# Sheet1.net
KiCad netlist of a schematic drawn in Altium Designer
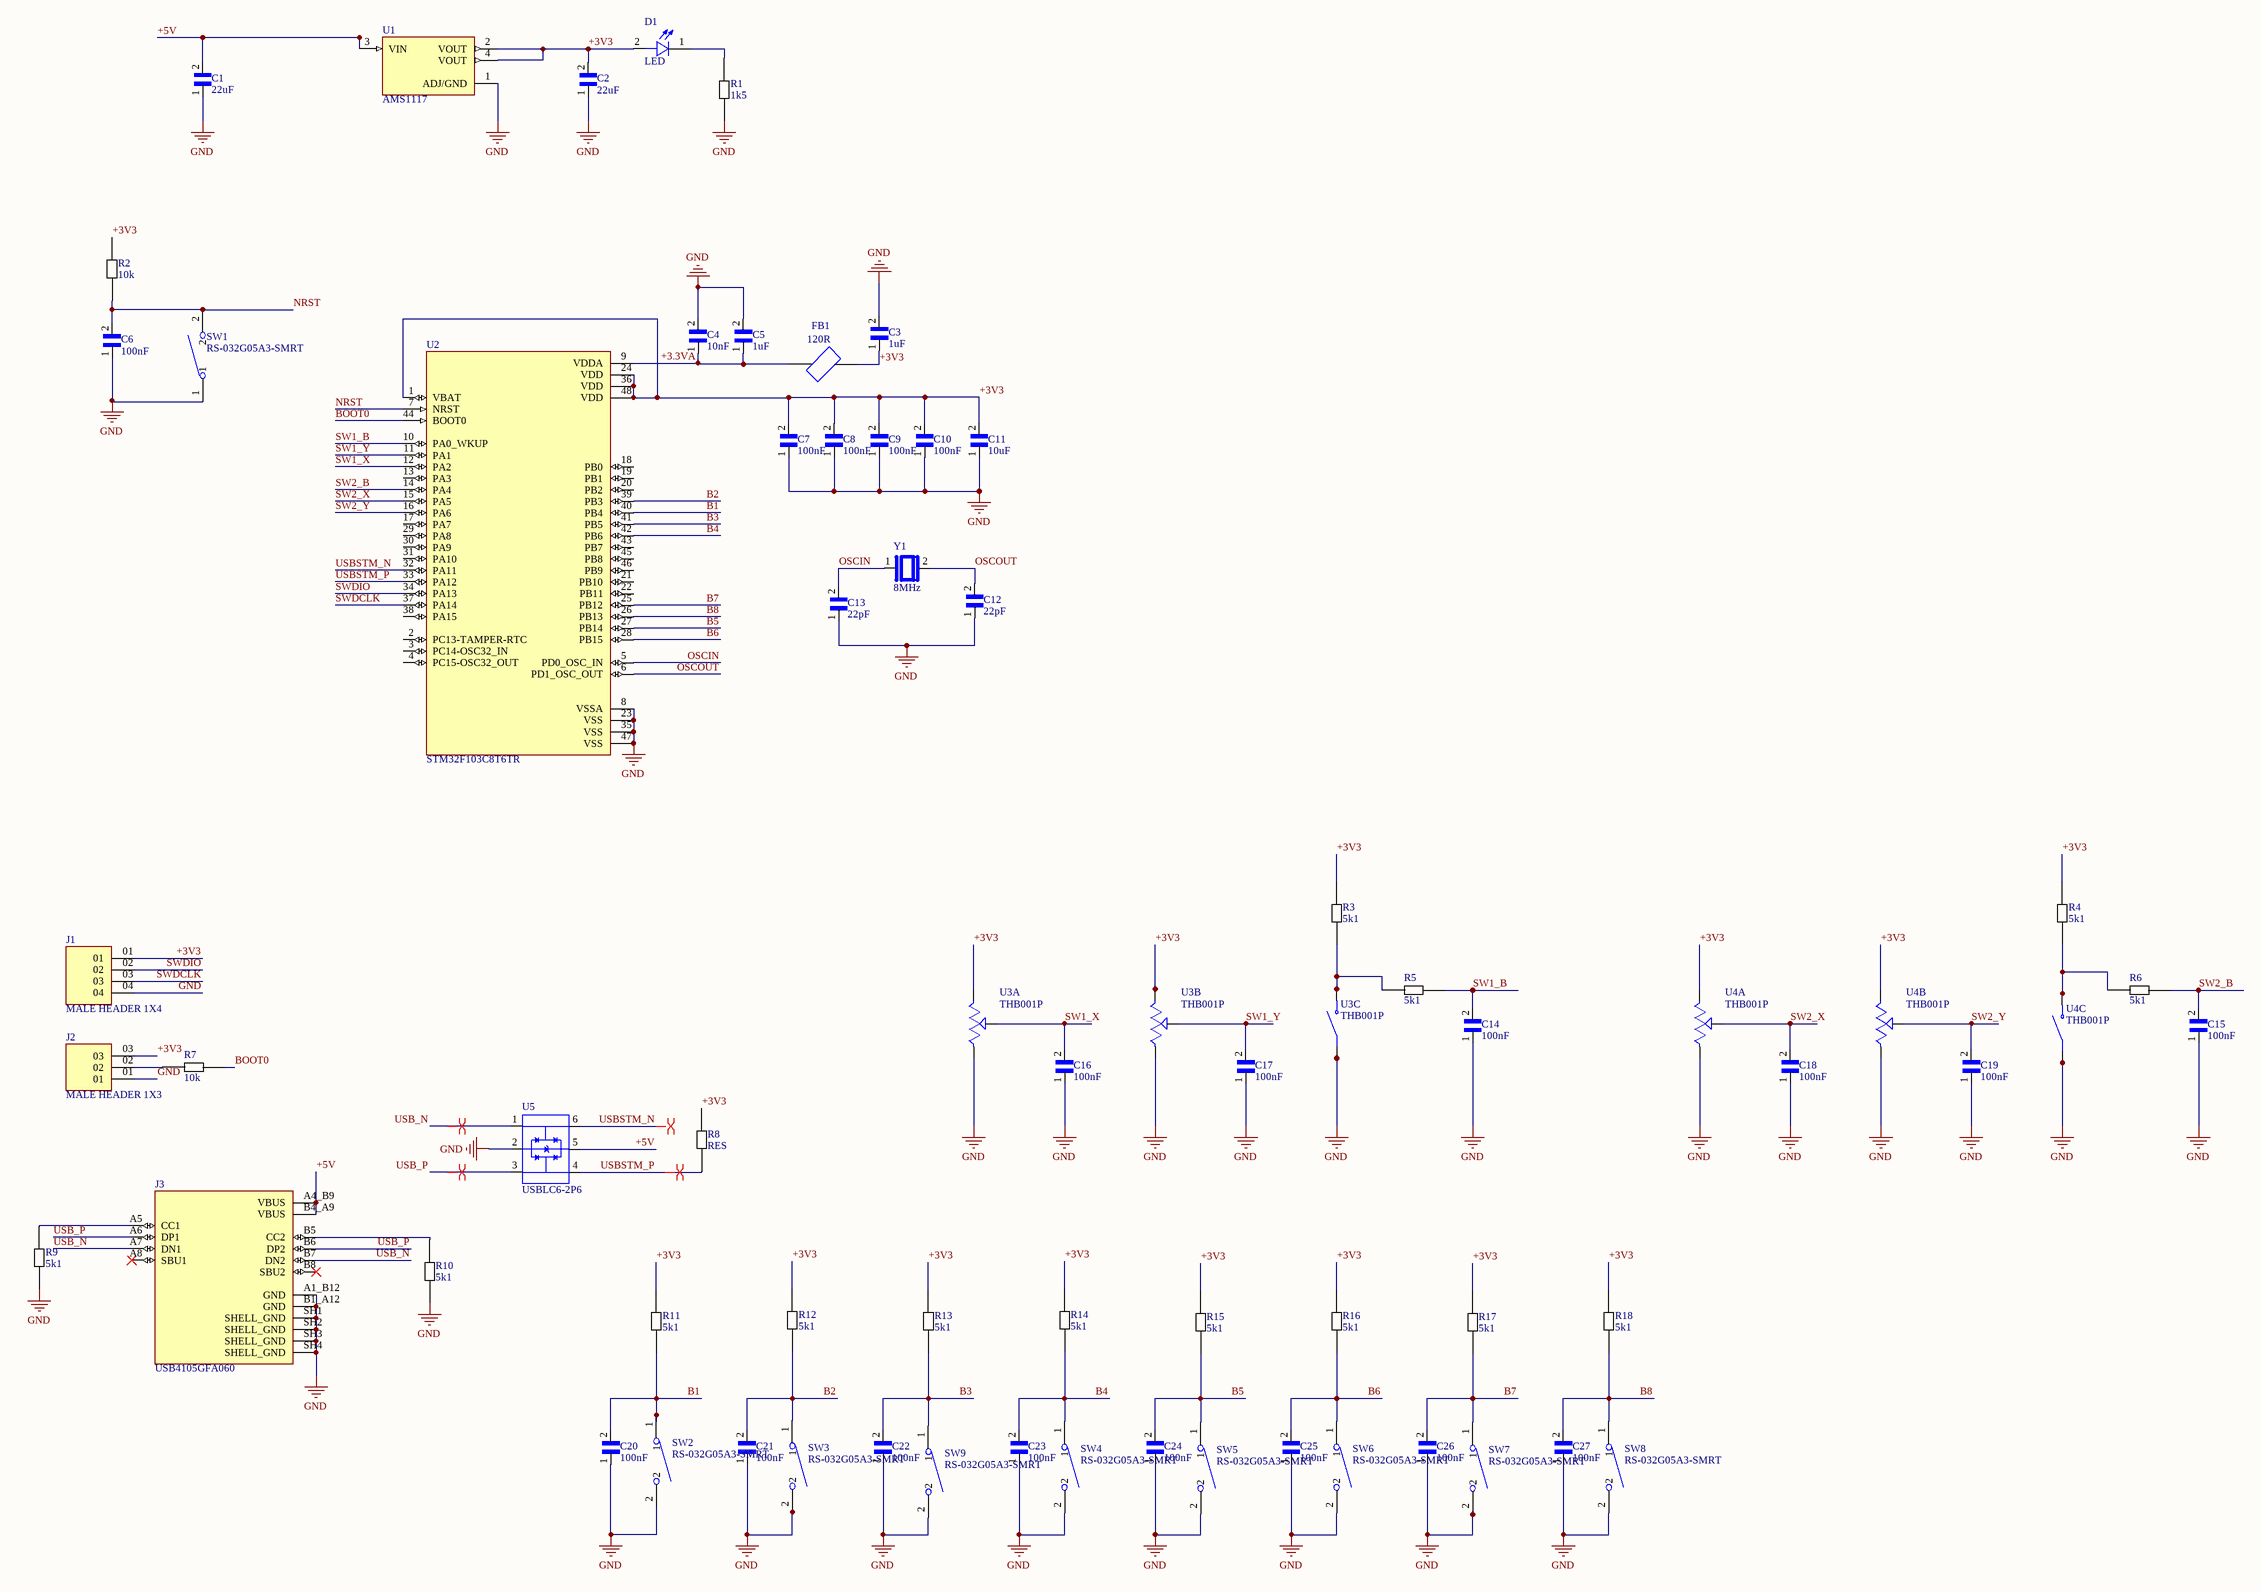
[diagram p0: Sheet1.SchDoc]

(export (version "E")
  (design (tool "Eeschema 10.0.6"))
  (components
    (comp (ref "C1")
      (value "22uF")
      (footprint "CAPC2012X94N")
      (description "10000pF Â±5% 16V Ceramic Capacitor X7R 0805 _2012 Metric_")
      (fields (field (name "MF") "AVX") (field (name "MP") "0805YC103J4T2A"))
      (libsource (lib "Schlib1") (part "CAP"))
    )
    (comp (ref "C2")
      (value "22uF")
      (footprint "CAPC2012X94N")
      (description "10000pF Â±5% 16V Ceramic Capacitor X7R 0805 _2012 Metric_")
      (fields (field (name "MF") "AVX") (field (name "MP") "0805YC103J4T2A"))
      (libsource (lib "Schlib1") (part "CAP"))
    )
    (comp (ref "C3")
      (value "1uF")
      (footprint "CAPC2012X94N")
      (description "10000pF Â±5% 16V Ceramic Capacitor X7R 0805 _2012 Metric_")
      (fields (field (name "MF") "AVX") (field (name "MP") "0805YC103J4T2A"))
      (libsource (lib "Schlib1") (part "CAP"))
    )
    (comp (ref "C4")
      (value "10nF")
      (footprint "CAPC2012X94N")
      (description "10000pF Â±5% 16V Ceramic Capacitor X7R 0805 _2012 Metric_")
      (fields (field (name "MF") "AVX") (field (name "MP") "0805YC103J4T2A"))
      (libsource (lib "Schlib1") (part "CAP"))
    )
    (comp (ref "C5")
      (value "1uF")
      (footprint "CAPC2012X94N")
      (description "10000pF Â±5% 16V Ceramic Capacitor X7R 0805 _2012 Metric_")
      (fields (field (name "MF") "AVX") (field (name "MP") "0805YC103J4T2A"))
      (libsource (lib "Schlib1") (part "CAP"))
    )
    (comp (ref "C6")
      (value "100nF")
      (footprint "CAPC2012X94N")
      (description "10000pF Â±5% 16V Ceramic Capacitor X7R 0805 _2012 Metric_")
      (fields (field (name "MF") "AVX") (field (name "MP") "0805YC103J4T2A"))
      (libsource (lib "Schlib1") (part "CAP"))
    )
    (comp (ref "C7")
      (value "100nF")
      (footprint "CAPC2012X94N")
      (description "10000pF Â±5% 16V Ceramic Capacitor X7R 0805 _2012 Metric_")
      (fields (field (name "MF") "AVX") (field (name "MP") "0805YC103J4T2A"))
      (libsource (lib "Schlib1") (part "CAP"))
    )
    (comp (ref "C8")
      (value "100nF")
      (footprint "CAPC2012X94N")
      (description "10000pF Â±5% 16V Ceramic Capacitor X7R 0805 _2012 Metric_")
      (fields (field (name "MF") "AVX") (field (name "MP") "0805YC103J4T2A"))
      (libsource (lib "Schlib1") (part "CAP"))
    )
    (comp (ref "C9")
      (value "100nF")
      (footprint "CAPC2012X94N")
      (description "10000pF Â±5% 16V Ceramic Capacitor X7R 0805 _2012 Metric_")
      (fields (field (name "MF") "AVX") (field (name "MP") "0805YC103J4T2A"))
      (libsource (lib "Schlib1") (part "CAP"))
    )
    (comp (ref "C10")
      (value "100nF")
      (footprint "CAPC2012X94N")
      (description "10000pF Â±5% 16V Ceramic Capacitor X7R 0805 _2012 Metric_")
      (fields (field (name "MF") "AVX") (field (name "MP") "0805YC103J4T2A"))
      (libsource (lib "Schlib1") (part "CAP"))
    )
    (comp (ref "C11")
      (value "10uF")
      (footprint "CAPC2012X94N")
      (description "10000pF Â±5% 16V Ceramic Capacitor X7R 0805 _2012 Metric_")
      (fields (field (name "MF") "AVX") (field (name "MP") "0805YC103J4T2A"))
      (libsource (lib "Schlib1") (part "CAP"))
    )
    (comp (ref "C12")
      (value "22pF")
      (footprint "CAPC2012X94N")
      (description "10000pF Â±5% 16V Ceramic Capacitor X7R 0805 _2012 Metric_")
      (fields (field (name "MF") "AVX") (field (name "MP") "0805YC103J4T2A"))
      (libsource (lib "Schlib1") (part "CAP"))
    )
    (comp (ref "C13")
      (value "22pF")
      (footprint "CAPC2012X94N")
      (description "10000pF Â±5% 16V Ceramic Capacitor X7R 0805 _2012 Metric_")
      (fields (field (name "MF") "AVX") (field (name "MP") "0805YC103J4T2A"))
      (libsource (lib "Schlib1") (part "CAP"))
    )
    (comp (ref "C14")
      (value "100nF")
      (footprint "CAPC2012X94N")
      (description "10000pF Â±5% 16V Ceramic Capacitor X7R 0805 _2012 Metric_")
      (fields (field (name "MF") "AVX") (field (name "MP") "0805YC103J4T2A"))
      (libsource (lib "Schlib1") (part "CAP"))
    )
    (comp (ref "C15")
      (value "100nF")
      (footprint "CAPC2012X94N")
      (description "10000pF Â±5% 16V Ceramic Capacitor X7R 0805 _2012 Metric_")
      (fields (field (name "MF") "AVX") (field (name "MP") "0805YC103J4T2A"))
      (libsource (lib "Schlib1") (part "CAP"))
    )
    (comp (ref "C16")
      (value "100nF")
      (footprint "CAPC2012X94N")
      (description "10000pF Â±5% 16V Ceramic Capacitor X7R 0805 _2012 Metric_")
      (fields (field (name "MF") "AVX") (field (name "MP") "0805YC103J4T2A"))
      (libsource (lib "Schlib1") (part "CAP"))
    )
    (comp (ref "C17")
      (value "100nF")
      (footprint "CAPC2012X94N")
      (description "10000pF Â±5% 16V Ceramic Capacitor X7R 0805 _2012 Metric_")
      (fields (field (name "MF") "AVX") (field (name "MP") "0805YC103J4T2A"))
      (libsource (lib "Schlib1") (part "CAP"))
    )
    (comp (ref "C18")
      (value "100nF")
      (footprint "CAPC2012X94N")
      (description "10000pF Â±5% 16V Ceramic Capacitor X7R 0805 _2012 Metric_")
      (fields (field (name "MF") "AVX") (field (name "MP") "0805YC103J4T2A"))
      (libsource (lib "Schlib1") (part "CAP"))
    )
    (comp (ref "C19")
      (value "100nF")
      (footprint "CAPC2012X94N")
      (description "10000pF Â±5% 16V Ceramic Capacitor X7R 0805 _2012 Metric_")
      (fields (field (name "MF") "AVX") (field (name "MP") "0805YC103J4T2A"))
      (libsource (lib "Schlib1") (part "CAP"))
    )
    (comp (ref "C20")
      (value "100nF")
      (footprint "CAPC2012X94N")
      (description "10000pF Â±5% 16V Ceramic Capacitor X7R 0805 _2012 Metric_")
      (fields (field (name "MF") "AVX") (field (name "MP") "0805YC103J4T2A"))
      (libsource (lib "Schlib1") (part "CAP"))
    )
    (comp (ref "C21")
      (value "100nF")
      (footprint "CAPC2012X94N")
      (description "10000pF Â±5% 16V Ceramic Capacitor X7R 0805 _2012 Metric_")
      (fields (field (name "MF") "AVX") (field (name "MP") "0805YC103J4T2A"))
      (libsource (lib "Schlib1") (part "CAP"))
    )
    (comp (ref "C22")
      (value "100nF")
      (footprint "CAPC2012X94N")
      (description "10000pF Â±5% 16V Ceramic Capacitor X7R 0805 _2012 Metric_")
      (fields (field (name "MF") "AVX") (field (name "MP") "0805YC103J4T2A"))
      (libsource (lib "Schlib1") (part "CAP"))
    )
    (comp (ref "C23")
      (value "100nF")
      (footprint "CAPC2012X94N")
      (description "10000pF Â±5% 16V Ceramic Capacitor X7R 0805 _2012 Metric_")
      (fields (field (name "MF") "AVX") (field (name "MP") "0805YC103J4T2A"))
      (libsource (lib "Schlib1") (part "CAP"))
    )
    (comp (ref "C24")
      (value "100nF")
      (footprint "CAPC2012X94N")
      (description "10000pF Â±5% 16V Ceramic Capacitor X7R 0805 _2012 Metric_")
      (fields (field (name "MF") "AVX") (field (name "MP") "0805YC103J4T2A"))
      (libsource (lib "Schlib1") (part "CAP"))
    )
    (comp (ref "C25")
      (value "100nF")
      (footprint "CAPC2012X94N")
      (description "10000pF Â±5% 16V Ceramic Capacitor X7R 0805 _2012 Metric_")
      (fields (field (name "MF") "AVX") (field (name "MP") "0805YC103J4T2A"))
      (libsource (lib "Schlib1") (part "CAP"))
    )
    (comp (ref "C26")
      (value "100nF")
      (footprint "CAPC2012X94N")
      (description "10000pF Â±5% 16V Ceramic Capacitor X7R 0805 _2012 Metric_")
      (fields (field (name "MF") "AVX") (field (name "MP") "0805YC103J4T2A"))
      (libsource (lib "Schlib1") (part "CAP"))
    )
    (comp (ref "C27")
      (value "100nF")
      (footprint "CAPC2012X94N")
      (description "10000pF Â±5% 16V Ceramic Capacitor X7R 0805 _2012 Metric_")
      (fields (field (name "MF") "AVX") (field (name "MP") "0805YC103J4T2A"))
      (libsource (lib "Schlib1") (part "CAP"))
    )
    (comp (ref "D1")
      (value "LED")
      (footprint "LED_V0805-SMD-R (Red)")
      (description "V0805 - Valcon 0805 Type Surface Mount LED")
      (fields (field (name "MF") "Valcon") (field (name "MP") "V0805-SMD-R (Red)"))
      (libsource (lib "Schlib1") (part "LED"))
    )
    (comp (ref "FB1")
      (value "120R")
      (footprint "FB_MI0805K400R-10")
      (description "40 Ohms @ 100MHz 1 Power Line Ferrite Bead 0805 (2012 Metric) 1.5A 50mOhm")
      (fields (field (name "MP") "MI0805K400R-10") (field (name "MF") "Laird-Signal Integrity Products"))
      (libsource (lib "Schlib1") (part "FB"))
    )
    (comp (ref "J1")
      (value "MALE HEADER 1X4")
      (footprint "SAMTEC_MTLW-104-X-X-S-X")
      (fields (field (name "MF") "{'manufacturer': u'Samtec Inc.'}") (field (name "MP") "MTLW-104-X-X-S-X"))
      (libsource (lib "Schlib1") (part "MALE HEADER 1X4"))
    )
    (comp (ref "J2")
      (value "MALE HEADER 1X3")
      (footprint "SAMTEC_MTLW-103-XX-XX-S-XXX")
      (description "Connector Header Through Hole 40 position 0.100\" (2.54mm)")
      (fields (field (name "MP") "MTLW-103-XX-XX-S-XXX"))
      (libsource (lib "Schlib1") (part "MALE HEADER 1X3"))
    )
    (comp (ref "J3")
      (value "USB4105GFA060")
      (footprint "GCT_USB4105GFA060")
      (fields (field (name "MF") "{'manufacturer': u'GCT'}"))
      (libsource (lib "Schlib1") (part "USB4105GFA060"))
    )
    (comp (ref "R1")
      (value "1k5")
      (footprint "RESC2012X60N")
      (description "330 Ohms Â±1% 0.125W, 1/8W Chip Resistor 0805 _2012 Metric_ Moisture Resistant Thick Film")
      (fields (field (name "MP") "RC0805FR-07330RL") (field (name "MF") "Yageo"))
      (libsource (lib "Schlib1") (part "RES"))
    )
    (comp (ref "R2")
      (value "10k")
      (footprint "RESC2012X60N")
      (description "330 Ohms Â±1% 0.125W, 1/8W Chip Resistor 0805 _2012 Metric_ Moisture Resistant Thick Film")
      (fields (field (name "MP") "RC0805FR-07330RL") (field (name "MF") "Yageo"))
      (libsource (lib "Schlib1") (part "RES"))
    )
    (comp (ref "R3")
      (value "5k1")
      (footprint "RESC2012X60N")
      (description "330 Ohms Â±1% 0.125W, 1/8W Chip Resistor 0805 _2012 Metric_ Moisture Resistant Thick Film")
      (fields (field (name "MP") "RC0805FR-07330RL") (field (name "MF") "Yageo"))
      (libsource (lib "Schlib1") (part "RES"))
    )
    (comp (ref "R4")
      (value "5k1")
      (footprint "RESC2012X60N")
      (description "330 Ohms Â±1% 0.125W, 1/8W Chip Resistor 0805 _2012 Metric_ Moisture Resistant Thick Film")
      (fields (field (name "MP") "RC0805FR-07330RL") (field (name "MF") "Yageo"))
      (libsource (lib "Schlib1") (part "RES"))
    )
    (comp (ref "R5")
      (value "5k1")
      (footprint "RESC2012X60N")
      (description "330 Ohms Â±1% 0.125W, 1/8W Chip Resistor 0805 _2012 Metric_ Moisture Resistant Thick Film")
      (fields (field (name "MP") "RC0805FR-07330RL") (field (name "MF") "Yageo"))
      (libsource (lib "Schlib1") (part "RES"))
    )
    (comp (ref "R6")
      (value "5k1")
      (footprint "RESC2012X60N")
      (description "330 Ohms Â±1% 0.125W, 1/8W Chip Resistor 0805 _2012 Metric_ Moisture Resistant Thick Film")
      (fields (field (name "MP") "RC0805FR-07330RL") (field (name "MF") "Yageo"))
      (libsource (lib "Schlib1") (part "RES"))
    )
    (comp (ref "R7")
      (value "10k")
      (footprint "RESC2012X60N")
      (description "330 Ohms Â±1% 0.125W, 1/8W Chip Resistor 0805 _2012 Metric_ Moisture Resistant Thick Film")
      (fields (field (name "MP") "RC0805FR-07330RL") (field (name "MF") "Yageo"))
      (libsource (lib "Schlib1") (part "RES"))
    )
    (comp (ref "R8")
      (value "RES")
      (footprint "RESC2012X60N")
      (description "330 Ohms Â±1% 0.125W, 1/8W Chip Resistor 0805 _2012 Metric_ Moisture Resistant Thick Film")
      (fields (field (name "MP") "RC0805FR-07330RL") (field (name "MF") "Yageo"))
      (libsource (lib "Schlib1") (part "RES"))
    )
    (comp (ref "R9")
      (value "5k1")
      (footprint "RESC2012X60N")
      (description "330 Ohms Â±1% 0.125W, 1/8W Chip Resistor 0805 _2012 Metric_ Moisture Resistant Thick Film")
      (fields (field (name "MP") "RC0805FR-07330RL") (field (name "MF") "Yageo"))
      (libsource (lib "Schlib1") (part "RES"))
    )
    (comp (ref "R10")
      (value "5k1")
      (footprint "RESC2012X60N")
      (description "330 Ohms Â±1% 0.125W, 1/8W Chip Resistor 0805 _2012 Metric_ Moisture Resistant Thick Film")
      (fields (field (name "MP") "RC0805FR-07330RL") (field (name "MF") "Yageo"))
      (libsource (lib "Schlib1") (part "RES"))
    )
    (comp (ref "R11")
      (value "5k1")
      (footprint "RESC2012X60N")
      (description "330 Ohms Â±1% 0.125W, 1/8W Chip Resistor 0805 _2012 Metric_ Moisture Resistant Thick Film")
      (fields (field (name "MP") "RC0805FR-07330RL") (field (name "MF") "Yageo"))
      (libsource (lib "Schlib1") (part "RES"))
    )
    (comp (ref "R12")
      (value "5k1")
      (footprint "RESC2012X60N")
      (description "330 Ohms Â±1% 0.125W, 1/8W Chip Resistor 0805 _2012 Metric_ Moisture Resistant Thick Film")
      (fields (field (name "MP") "RC0805FR-07330RL") (field (name "MF") "Yageo"))
      (libsource (lib "Schlib1") (part "RES"))
    )
    (comp (ref "R13")
      (value "5k1")
      (footprint "RESC2012X60N")
      (description "330 Ohms Â±1% 0.125W, 1/8W Chip Resistor 0805 _2012 Metric_ Moisture Resistant Thick Film")
      (fields (field (name "MP") "RC0805FR-07330RL") (field (name "MF") "Yageo"))
      (libsource (lib "Schlib1") (part "RES"))
    )
    (comp (ref "R14")
      (value "5k1")
      (footprint "RESC2012X60N")
      (description "330 Ohms Â±1% 0.125W, 1/8W Chip Resistor 0805 _2012 Metric_ Moisture Resistant Thick Film")
      (fields (field (name "MP") "RC0805FR-07330RL") (field (name "MF") "Yageo"))
      (libsource (lib "Schlib1") (part "RES"))
    )
    (comp (ref "R15")
      (value "5k1")
      (footprint "RESC2012X60N")
      (description "330 Ohms Â±1% 0.125W, 1/8W Chip Resistor 0805 _2012 Metric_ Moisture Resistant Thick Film")
      (fields (field (name "MP") "RC0805FR-07330RL") (field (name "MF") "Yageo"))
      (libsource (lib "Schlib1") (part "RES"))
    )
    (comp (ref "R16")
      (value "5k1")
      (footprint "RESC2012X60N")
      (description "330 Ohms Â±1% 0.125W, 1/8W Chip Resistor 0805 _2012 Metric_ Moisture Resistant Thick Film")
      (fields (field (name "MP") "RC0805FR-07330RL") (field (name "MF") "Yageo"))
      (libsource (lib "Schlib1") (part "RES"))
    )
    (comp (ref "R17")
      (value "5k1")
      (footprint "RESC2012X60N")
      (description "330 Ohms Â±1% 0.125W, 1/8W Chip Resistor 0805 _2012 Metric_ Moisture Resistant Thick Film")
      (fields (field (name "MP") "RC0805FR-07330RL") (field (name "MF") "Yageo"))
      (libsource (lib "Schlib1") (part "RES"))
    )
    (comp (ref "R18")
      (value "5k1")
      (footprint "RESC2012X60N")
      (description "330 Ohms Â±1% 0.125W, 1/8W Chip Resistor 0805 _2012 Metric_ Moisture Resistant Thick Film")
      (fields (field (name "MP") "RC0805FR-07330RL") (field (name "MF") "Yageo"))
      (libsource (lib "Schlib1") (part "RES"))
    )
    (comp (ref "SW1")
      (value "RS-032G05A3-SMRT")
      (footprint "SW_RS-032G05A3-SMRT")
      (description "Tactile Switch SPST-NO Top Actuated Surface Mount")
      (fields (field (name "MF") "C&K") (field (name "MP") "RS032G05A3SMRT"))
      (libsource (lib "Schlib1") (part "RS-032G05A3-SMRT"))
    )
    (comp (ref "SW2")
      (value "RS-032G05A3-SMRT")
      (footprint "SW_RS-032G05A3-SMRT")
      (description "Tactile Switch SPST-NO Top Actuated Surface Mount")
      (fields (field (name "MF") "C&K") (field (name "MP") "RS032G05A3SMRT"))
      (libsource (lib "Schlib1") (part "RS-032G05A3-SMRT"))
    )
    (comp (ref "SW3")
      (value "RS-032G05A3-SMRT")
      (footprint "SW_RS-032G05A3-SMRT")
      (description "Tactile Switch SPST-NO Top Actuated Surface Mount")
      (fields (field (name "MF") "C&K") (field (name "MP") "RS032G05A3SMRT"))
      (libsource (lib "Schlib1") (part "RS-032G05A3-SMRT"))
    )
    (comp (ref "SW4")
      (value "RS-032G05A3-SMRT")
      (footprint "SW_RS-032G05A3-SMRT")
      (description "Tactile Switch SPST-NO Top Actuated Surface Mount")
      (fields (field (name "MF") "C&K") (field (name "MP") "RS032G05A3SMRT"))
      (libsource (lib "Schlib1") (part "RS-032G05A3-SMRT"))
    )
    (comp (ref "SW5")
      (value "RS-032G05A3-SMRT")
      (footprint "SW_RS-032G05A3-SMRT")
      (description "Tactile Switch SPST-NO Top Actuated Surface Mount")
      (fields (field (name "MF") "C&K") (field (name "MP") "RS032G05A3SMRT"))
      (libsource (lib "Schlib1") (part "RS-032G05A3-SMRT"))
    )
    (comp (ref "SW6")
      (value "RS-032G05A3-SMRT")
      (footprint "SW_RS-032G05A3-SMRT")
      (description "Tactile Switch SPST-NO Top Actuated Surface Mount")
      (fields (field (name "MF") "C&K") (field (name "MP") "RS032G05A3SMRT"))
      (libsource (lib "Schlib1") (part "RS-032G05A3-SMRT"))
    )
    (comp (ref "SW7")
      (value "RS-032G05A3-SMRT")
      (footprint "SW_RS-032G05A3-SMRT")
      (description "Tactile Switch SPST-NO Top Actuated Surface Mount")
      (fields (field (name "MF") "C&K") (field (name "MP") "RS032G05A3SMRT"))
      (libsource (lib "Schlib1") (part "RS-032G05A3-SMRT"))
    )
    (comp (ref "SW8")
      (value "RS-032G05A3-SMRT")
      (footprint "SW_RS-032G05A3-SMRT")
      (description "Tactile Switch SPST-NO Top Actuated Surface Mount")
      (fields (field (name "MF") "C&K") (field (name "MP") "RS032G05A3SMRT"))
      (libsource (lib "Schlib1") (part "RS-032G05A3-SMRT"))
    )
    (comp (ref "SW9")
      (value "RS-032G05A3-SMRT")
      (footprint "SW_RS-032G05A3-SMRT")
      (description "Tactile Switch SPST-NO Top Actuated Surface Mount")
      (fields (field (name "MF") "C&K") (field (name "MP") "RS032G05A3SMRT"))
      (libsource (lib "Schlib1") (part "RS-032G05A3-SMRT"))
    )
    (comp (ref "U1")
      (value "AMS1117")
      (footprint "SOT229P700X180-4N")
      (description "1A LOW DROPOUT VOLTAGE REGULATOR SOT-223")
      (fields (field (name "MF") "Advanced Monolithic Systems"))
      (libsource (lib "Schlib1") (part "AMS1117"))
    )
    (comp (ref "U2")
      (value "STM32F103C8T6TR")
      (footprint "QFP50P900X900X160-48N")
      (fields (field (name "MF") "{'manufacturer': u'STMicroelectronics'}"))
      (libsource (lib "Schlib1") (part "STM32F103C8T6TR"))
    )
    (comp (ref "U3")
      (value "THB001P")
      (footprint "CNK_THB001P")
      (description "Joystick, 2 - Axis Analog (Resistive) Output")
      (fields (field (name "MF") "C&K"))
      (libsource (lib "") (part "THB001P_1"))
    )
    (comp (ref "U4")
      (value "THB001P")
      (footprint "CNK_THB001P")
      (description "Joystick, 2 - Axis Analog (Resistive) Output")
      (fields (field (name "MF") "C&K"))
      (libsource (lib "Schlib1") (part "THB001P"))
    )
    (comp (ref "U5")
      (value "USBLC6-2P6")
      (footprint "SOT50P160X60-6N")
      (description "17V Clamp 5A _8/20Âµs_ Ipp Tvs Diode Surface Mount SOT-666")
      (fields (field (name "MF") "STMicroelectronics"))
      (libsource (lib "Schlib1") (part "USBLC6-2P6"))
    )
    (comp (ref "Y1")
      (value "8MHz")
      (footprint "XTAL_HC49P488W43L1150T466H350")
      (description "16 MHz Â±30ppm Crystal 18pF 50 Ohms HC-49/US")
      (fields (field (name "MF") "Citizen Finedevice Co Ltd") (field (name "MP") "HC-49/U-S16000000ABJB"))
      (libsource (lib "Schlib1") (part "HC-49/U-S16000000ABJB"))
    )
  )
  (nets
    (net (code "1") (name "/+3.3VA") (class "Default")
      (node (ref "C4") (pin "1") (pinfunction "1_1") (pintype "passive"))
      (node (ref "C5") (pin "1") (pinfunction "1_1") (pintype "passive"))
      (node (ref "FB1") (pin "1") (pinfunction "1_1") (pintype "passive"))
      (node (ref "U2") (pin "9") (pinfunction "VDDA_9") (pintype "power_in"))
    )
    (net (code "2") (name "/+3V3") (class "Default")
      (node (ref "C10") (pin "2") (pinfunction "2_2") (pintype "passive"))
      (node (ref "C11") (pin "2") (pinfunction "2_2") (pintype "passive"))
      (node (ref "C2") (pin "2") (pinfunction "2_2") (pintype "passive"))
      (node (ref "C3") (pin "1") (pinfunction "1_1") (pintype "passive"))
      (node (ref "C7") (pin "2") (pinfunction "2_2") (pintype "passive"))
      (node (ref "C8") (pin "2") (pinfunction "2_2") (pintype "passive"))
      (node (ref "C9") (pin "2") (pinfunction "2_2") (pintype "passive"))
      (node (ref "D1") (pin "2") (pinfunction "A_2") (pintype "passive"))
      (node (ref "FB1") (pin "2") (pinfunction "2_2") (pintype "passive"))
      (node (ref "J1") (pin "01") (pinfunction "01_01") (pintype "passive"))
      (node (ref "J2") (pin "03") (pinfunction "03_03") (pintype "passive"))
      (node (ref "R11") (pin "2") (pinfunction "2_2") (pintype "passive"))
      (node (ref "R12") (pin "2") (pinfunction "2_2") (pintype "passive"))
      (node (ref "R13") (pin "2") (pinfunction "2_2") (pintype "passive"))
      (node (ref "R14") (pin "2") (pinfunction "2_2") (pintype "passive"))
      (node (ref "R15") (pin "2") (pinfunction "2_2") (pintype "passive"))
      (node (ref "R16") (pin "2") (pinfunction "2_2") (pintype "passive"))
      (node (ref "R17") (pin "2") (pinfunction "2_2") (pintype "passive"))
      (node (ref "R18") (pin "2") (pinfunction "2_2") (pintype "passive"))
      (node (ref "R2") (pin "2") (pinfunction "2_2") (pintype "passive"))
      (node (ref "R3") (pin "2") (pinfunction "2_2") (pintype "passive"))
      (node (ref "R4") (pin "2") (pinfunction "2_2") (pintype "passive"))
      (node (ref "R8") (pin "2") (pinfunction "2_2") (pintype "passive"))
      (node (ref "U1") (pin "2") (pinfunction "VOUT_2") (pintype "output"))
      (node (ref "U1") (pin "4") (pinfunction "VOUT_4") (pintype "output"))
      (node (ref "U2") (pin "1") (pinfunction "VBAT_1") (pintype "bidirectional"))
      (node (ref "U2") (pin "24") (pinfunction "VDD_24") (pintype "power_in"))
      (node (ref "U2") (pin "36") (pinfunction "VDD_36") (pintype "power_in"))
      (node (ref "U2") (pin "48") (pinfunction "VDD_48") (pintype "power_in"))
      (node (ref "U3") (pin "VR1_3") (pinfunction "VR1_3_VR1_3") (pintype "passive"))
      (node (ref "U3") (pin "VR2_3") (pinfunction "VR2_3_VR2_3") (pintype "passive"))
      (node (ref "U4") (pin "VR1_3") (pinfunction "VR1_3_VR1_3") (pintype "passive"))
      (node (ref "U4") (pin "VR2_3") (pinfunction "VR2_3_VR2_3") (pintype "passive"))
    )
    (net (code "3") (name "/+5V") (class "Default")
      (node (ref "C1") (pin "2") (pinfunction "2_2") (pintype "passive"))
      (node (ref "J3") (pin "A4_B9") (pinfunction "VBUS_A4_B9") (pintype "power_in"))
      (node (ref "J3") (pin "B4_A9") (pinfunction "VBUS_B4_A9") (pintype "power_in"))
      (node (ref "U1") (pin "3") (pinfunction "VIN_3") (pintype "input"))
      (node (ref "U5") (pin "5") (pinfunction "VBUS_5") (pintype "power_in"))
    )
    (net (code "4") (name "/B1") (class "Default")
      (node (ref "C20") (pin "2") (pinfunction "2_2") (pintype "passive"))
      (node (ref "R11") (pin "1") (pinfunction "1_1") (pintype "passive"))
      (node (ref "SW2") (pin "1") (pinfunction "1_1") (pintype "passive"))
      (node (ref "U2") (pin "40") (pinfunction "PB4_40") (pintype "bidirectional"))
    )
    (net (code "5") (name "/B2") (class "Default")
      (node (ref "C21") (pin "2") (pinfunction "2_2") (pintype "passive"))
      (node (ref "R12") (pin "1") (pinfunction "1_1") (pintype "passive"))
      (node (ref "SW3") (pin "1") (pinfunction "1_1") (pintype "passive"))
      (node (ref "U2") (pin "39") (pinfunction "PB3_39") (pintype "bidirectional"))
    )
    (net (code "6") (name "/B3") (class "Default")
      (node (ref "C22") (pin "2") (pinfunction "2_2") (pintype "passive"))
      (node (ref "R13") (pin "1") (pinfunction "1_1") (pintype "passive"))
      (node (ref "SW9") (pin "1") (pinfunction "1_1") (pintype "passive"))
      (node (ref "U2") (pin "41") (pinfunction "PB5_41") (pintype "bidirectional"))
    )
    (net (code "7") (name "/B4") (class "Default")
      (node (ref "C23") (pin "2") (pinfunction "2_2") (pintype "passive"))
      (node (ref "R14") (pin "1") (pinfunction "1_1") (pintype "passive"))
      (node (ref "SW4") (pin "1") (pinfunction "1_1") (pintype "passive"))
      (node (ref "U2") (pin "42") (pinfunction "PB6_42") (pintype "bidirectional"))
    )
    (net (code "8") (name "/B5") (class "Default")
      (node (ref "C24") (pin "2") (pinfunction "2_2") (pintype "passive"))
      (node (ref "R15") (pin "1") (pinfunction "1_1") (pintype "passive"))
      (node (ref "SW5") (pin "1") (pinfunction "1_1") (pintype "passive"))
      (node (ref "U2") (pin "27") (pinfunction "PB14_27") (pintype "bidirectional"))
    )
    (net (code "9") (name "/B6") (class "Default")
      (node (ref "C25") (pin "2") (pinfunction "2_2") (pintype "passive"))
      (node (ref "R16") (pin "1") (pinfunction "1_1") (pintype "passive"))
      (node (ref "SW6") (pin "1") (pinfunction "1_1") (pintype "passive"))
      (node (ref "U2") (pin "28") (pinfunction "PB15_28") (pintype "bidirectional"))
    )
    (net (code "10") (name "/B7") (class "Default")
      (node (ref "C26") (pin "2") (pinfunction "2_2") (pintype "passive"))
      (node (ref "R17") (pin "1") (pinfunction "1_1") (pintype "passive"))
      (node (ref "SW7") (pin "1") (pinfunction "1_1") (pintype "passive"))
      (node (ref "U2") (pin "25") (pinfunction "PB12_25") (pintype "bidirectional"))
    )
    (net (code "11") (name "/B8") (class "Default")
      (node (ref "C27") (pin "2") (pinfunction "2_2") (pintype "passive"))
      (node (ref "R18") (pin "1") (pinfunction "1_1") (pintype "passive"))
      (node (ref "SW8") (pin "1") (pinfunction "1_1") (pintype "passive"))
      (node (ref "U2") (pin "26") (pinfunction "PB13_26") (pintype "bidirectional"))
    )
    (net (code "12") (name "/BOOT0") (class "Default")
      (node (ref "R7") (pin "2") (pinfunction "2_2") (pintype "passive"))
      (node (ref "U2") (pin "44") (pinfunction "BOOT0_44") (pintype "input"))
    )
    (net (code "13") (name "/NRST") (class "Default")
      (node (ref "C6") (pin "2") (pinfunction "2_2") (pintype "passive"))
      (node (ref "R2") (pin "1") (pinfunction "1_1") (pintype "passive"))
      (node (ref "SW1") (pin "2") (pinfunction "2_2") (pintype "passive"))
      (node (ref "U2") (pin "7") (pinfunction "NRST_7") (pintype "input"))
    )
    (net (code "14") (name "/OSCIN") (class "Default")
      (node (ref "C13") (pin "2") (pinfunction "2_2") (pintype "passive"))
      (node (ref "U2") (pin "5") (pinfunction "PD0_OSC_IN_5") (pintype "bidirectional"))
      (node (ref "Y1") (pin "1") (pinfunction "1_1") (pintype "passive"))
    )
    (net (code "15") (name "/OSCOUT") (class "Default")
      (node (ref "C12") (pin "2") (pinfunction "2_2") (pintype "passive"))
      (node (ref "U2") (pin "6") (pinfunction "PD1_OSC_OUT_6") (pintype "bidirectional"))
      (node (ref "Y1") (pin "2") (pinfunction "2_2") (pintype "passive"))
    )
    (net (code "16") (name "/SW1_B") (class "Default")
      (node (ref "C14") (pin "2") (pinfunction "2_2") (pintype "passive"))
      (node (ref "R5") (pin "1") (pinfunction "1_1") (pintype "passive"))
      (node (ref "U2") (pin "10") (pinfunction "PA0_WKUP_10") (pintype "bidirectional"))
    )
    (net (code "17") (name "/SW1_X") (class "Default")
      (node (ref "C16") (pin "2") (pinfunction "2_2") (pintype "passive"))
      (node (ref "U2") (pin "12") (pinfunction "PA2_12") (pintype "bidirectional"))
      (node (ref "U3") (pin "VR1_2") (pinfunction "VR1_2_VR1_2") (pintype "passive"))
    )
    (net (code "18") (name "/SW1_Y") (class "Default")
      (node (ref "C17") (pin "2") (pinfunction "2_2") (pintype "passive"))
      (node (ref "U2") (pin "11") (pinfunction "PA1_11") (pintype "bidirectional"))
      (node (ref "U3") (pin "VR2_2") (pinfunction "VR2_2_VR2_2") (pintype "passive"))
    )
    (net (code "19") (name "/SW2_B") (class "Default")
      (node (ref "C15") (pin "2") (pinfunction "2_2") (pintype "passive"))
      (node (ref "R6") (pin "1") (pinfunction "1_1") (pintype "passive"))
      (node (ref "U2") (pin "14") (pinfunction "PA4_14") (pintype "bidirectional"))
    )
    (net (code "20") (name "/SW2_X") (class "Default")
      (node (ref "C18") (pin "2") (pinfunction "2_2") (pintype "passive"))
      (node (ref "U2") (pin "15") (pinfunction "PA5_15") (pintype "bidirectional"))
      (node (ref "U4") (pin "VR1_2") (pinfunction "VR1_2_VR1_2") (pintype "passive"))
    )
    (net (code "21") (name "/SW2_Y") (class "Default")
      (node (ref "C19") (pin "2") (pinfunction "2_2") (pintype "passive"))
      (node (ref "U2") (pin "16") (pinfunction "PA6_16") (pintype "bidirectional"))
      (node (ref "U4") (pin "VR2_2") (pinfunction "VR2_2_VR2_2") (pintype "passive"))
    )
    (net (code "22") (name "/SWDCLK") (class "Default")
      (node (ref "J1") (pin "03") (pinfunction "03_03") (pintype "passive"))
      (node (ref "U2") (pin "37") (pinfunction "PA14_37") (pintype "bidirectional"))
    )
    (net (code "23") (name "/SWDIO") (class "Default")
      (node (ref "J1") (pin "02") (pinfunction "02_02") (pintype "passive"))
      (node (ref "U2") (pin "34") (pinfunction "PA13_34") (pintype "bidirectional"))
    )
    (net (code "24") (name "/USBSTM_N") (class "Default")
      (node (ref "U2") (pin "32") (pinfunction "PA11_32") (pintype "bidirectional"))
      (node (ref "U5") (pin "6") (pinfunction "I/O1_2_6") (pintype "bidirectional"))
    )
    (net (code "25") (name "/USBSTM_P") (class "Default")
      (node (ref "R8") (pin "1") (pinfunction "1_1") (pintype "passive"))
      (node (ref "U2") (pin "33") (pinfunction "PA12_33") (pintype "bidirectional"))
      (node (ref "U5") (pin "4") (pinfunction "I/O2_2_4") (pintype "bidirectional"))
    )
    (net (code "26") (name "/USB_N") (class "Default")
      (node (ref "J3") (pin "A7") (pinfunction "DN1_A7") (pintype "bidirectional"))
      (node (ref "J3") (pin "B7") (pinfunction "DN2_B7") (pintype "bidirectional"))
      (node (ref "U5") (pin "1") (pinfunction "I/O1_1_1") (pintype "bidirectional"))
    )
    (net (code "27") (name "/USB_P") (class "Default")
      (node (ref "J3") (pin "A6") (pinfunction "DP1_A6") (pintype "bidirectional"))
      (node (ref "J3") (pin "B6") (pinfunction "DP2_B6") (pintype "bidirectional"))
      (node (ref "U5") (pin "3") (pinfunction "I/O2_1_3") (pintype "bidirectional"))
    )
    (net (code "28") (name "GND") (class "Default")
      (node (ref "C1") (pin "1") (pinfunction "1_1") (pintype "passive"))
      (node (ref "C10") (pin "1") (pinfunction "1_1") (pintype "passive"))
      (node (ref "C11") (pin "1") (pinfunction "1_1") (pintype "passive"))
      (node (ref "C12") (pin "1") (pinfunction "1_1") (pintype "passive"))
      (node (ref "C13") (pin "1") (pinfunction "1_1") (pintype "passive"))
      (node (ref "C14") (pin "1") (pinfunction "1_1") (pintype "passive"))
      (node (ref "C15") (pin "1") (pinfunction "1_1") (pintype "passive"))
      (node (ref "C16") (pin "1") (pinfunction "1_1") (pintype "passive"))
      (node (ref "C17") (pin "1") (pinfunction "1_1") (pintype "passive"))
      (node (ref "C18") (pin "1") (pinfunction "1_1") (pintype "passive"))
      (node (ref "C19") (pin "1") (pinfunction "1_1") (pintype "passive"))
      (node (ref "C2") (pin "1") (pinfunction "1_1") (pintype "passive"))
      (node (ref "C20") (pin "1") (pinfunction "1_1") (pintype "passive"))
      (node (ref "C21") (pin "1") (pinfunction "1_1") (pintype "passive"))
      (node (ref "C22") (pin "1") (pinfunction "1_1") (pintype "passive"))
      (node (ref "C23") (pin "1") (pinfunction "1_1") (pintype "passive"))
      (node (ref "C24") (pin "1") (pinfunction "1_1") (pintype "passive"))
      (node (ref "C25") (pin "1") (pinfunction "1_1") (pintype "passive"))
      (node (ref "C26") (pin "1") (pinfunction "1_1") (pintype "passive"))
      (node (ref "C27") (pin "1") (pinfunction "1_1") (pintype "passive"))
      (node (ref "C3") (pin "2") (pinfunction "2_2") (pintype "passive"))
      (node (ref "C4") (pin "2") (pinfunction "2_2") (pintype "passive"))
      (node (ref "C5") (pin "2") (pinfunction "2_2") (pintype "passive"))
      (node (ref "C6") (pin "1") (pinfunction "1_1") (pintype "passive"))
      (node (ref "C7") (pin "1") (pinfunction "1_1") (pintype "passive"))
      (node (ref "C8") (pin "1") (pinfunction "1_1") (pintype "passive"))
      (node (ref "C9") (pin "1") (pinfunction "1_1") (pintype "passive"))
      (node (ref "J1") (pin "04") (pinfunction "04_04") (pintype "passive"))
      (node (ref "J2") (pin "01") (pinfunction "01_01") (pintype "passive"))
      (node (ref "J3") (pin "A1_B12") (pinfunction "GND_A1_B12") (pintype "power_in"))
      (node (ref "J3") (pin "B1_A12") (pinfunction "GND_B1_A12") (pintype "power_in"))
      (node (ref "J3") (pin "SH1") (pinfunction "SHELL_GND_SH1") (pintype "power_in"))
      (node (ref "J3") (pin "SH2") (pinfunction "SHELL_GND_SH2") (pintype "power_in"))
      (node (ref "J3") (pin "SH3") (pinfunction "SHELL_GND_SH3") (pintype "power_in"))
      (node (ref "J3") (pin "SH4") (pinfunction "SHELL_GND_SH4") (pintype "power_in"))
      (node (ref "R1") (pin "1") (pinfunction "1_1") (pintype "passive"))
      (node (ref "R10") (pin "1") (pinfunction "1_1") (pintype "passive"))
      (node (ref "R9") (pin "1") (pinfunction "1_1") (pintype "passive"))
      (node (ref "SW1") (pin "1") (pinfunction "1_1") (pintype "passive"))
      (node (ref "SW2") (pin "2") (pinfunction "2_2") (pintype "passive"))
      (node (ref "SW3") (pin "2") (pinfunction "2_2") (pintype "passive"))
      (node (ref "SW4") (pin "2") (pinfunction "2_2") (pintype "passive"))
      (node (ref "SW5") (pin "2") (pinfunction "2_2") (pintype "passive"))
      (node (ref "SW6") (pin "2") (pinfunction "2_2") (pintype "passive"))
      (node (ref "SW7") (pin "2") (pinfunction "2_2") (pintype "passive"))
      (node (ref "SW8") (pin "2") (pinfunction "2_2") (pintype "passive"))
      (node (ref "SW9") (pin "2") (pinfunction "2_2") (pintype "passive"))
      (node (ref "U1") (pin "1") (pinfunction "ADJ/GND_1") (pintype "power_in"))
      (node (ref "U2") (pin "23") (pinfunction "VSS_23") (pintype "power_in"))
      (node (ref "U2") (pin "35") (pinfunction "VSS_35") (pintype "power_in"))
      (node (ref "U2") (pin "47") (pinfunction "VSS_47") (pintype "power_in"))
      (node (ref "U2") (pin "8") (pinfunction "VSSA_8") (pintype "power_in"))
      (node (ref "U3") (pin "C") (pinfunction "COM_C") (pintype "passive"))
      (node (ref "U3") (pin "D") (pinfunction "COM_D") (pintype "passive"))
      (node (ref "U3") (pin "VR1_1") (pinfunction "VR1_1_VR1_1") (pintype "passive"))
      (node (ref "U3") (pin "VR2_1") (pinfunction "VR2_1_VR2_1") (pintype "passive"))
      (node (ref "U4") (pin "C") (pinfunction "COM_C") (pintype "passive"))
      (node (ref "U4") (pin "D") (pinfunction "COM_D") (pintype "passive"))
      (node (ref "U4") (pin "VR1_1") (pinfunction "VR1_1_VR1_1") (pintype "passive"))
      (node (ref "U4") (pin "VR2_1") (pinfunction "VR2_1_VR2_1") (pintype "passive"))
      (node (ref "U5") (pin "2") (pinfunction "GND_2") (pintype "power_in"))
    )
    (net (code "29") (name "Net-(D1-C)") (class "Default")
      (node (ref "D1") (pin "1") (pinfunction "C_1") (pintype "passive"))
      (node (ref "R1") (pin "2") (pinfunction "2_2") (pintype "passive"))
    )
    (net (code "30") (name "Net-(J2-Pad02)") (class "Default")
      (node (ref "J2") (pin "02") (pinfunction "02_02") (pintype "passive"))
      (node (ref "R7") (pin "1") (pinfunction "1_1") (pintype "passive"))
    )
    (net (code "31") (name "Net-(J3-CC1)") (class "Default")
      (node (ref "J3") (pin "A5") (pinfunction "CC1_A5") (pintype "bidirectional"))
      (node (ref "R9") (pin "2") (pinfunction "2_2") (pintype "passive"))
    )
    (net (code "32") (name "Net-(J3-CC2)") (class "Default")
      (node (ref "J3") (pin "B5") (pinfunction "CC2_B5") (pintype "bidirectional"))
      (node (ref "R10") (pin "2") (pinfunction "2_2") (pintype "passive"))
    )
    (net (code "33") (name "Net-(R3-Pad1)") (class "Default")
      (node (ref "R3") (pin "1") (pinfunction "1_1") (pintype "passive"))
      (node (ref "R5") (pin "2") (pinfunction "2_2") (pintype "passive"))
      (node (ref "U3") (pin "A") (pinfunction "NO_A") (pintype "passive"))
      (node (ref "U3") (pin "B") (pinfunction "NO_B") (pintype "passive"))
    )
    (net (code "34") (name "Net-(R4-Pad1)") (class "Default")
      (node (ref "R4") (pin "1") (pinfunction "1_1") (pintype "passive"))
      (node (ref "R6") (pin "2") (pinfunction "2_2") (pintype "passive"))
      (node (ref "U4") (pin "A") (pinfunction "NO_A") (pintype "passive"))
      (node (ref "U4") (pin "B") (pinfunction "NO_B") (pintype "passive"))
    )
    (net (code "35") (name "unconnected-(J3-SBU1-PadA8)") (class "Default")
      (node (ref "J3") (pin "A8") (pinfunction "SBU1_A8") (pintype "bidirectional+no_connect"))
    )
    (net (code "36") (name "unconnected-(J3-SBU2-PadB8)") (class "Default")
      (node (ref "J3") (pin "B8") (pinfunction "SBU2_B8") (pintype "bidirectional+no_connect"))
    )
    (net (code "37") (name "unconnected-(U2-PA3-Pad13)") (class "Default")
      (node (ref "U2") (pin "13") (pinfunction "PA3_13") (pintype "bidirectional"))
    )
    (net (code "38") (name "unconnected-(U2-PA7-Pad17)") (class "Default")
      (node (ref "U2") (pin "17") (pinfunction "PA7_17") (pintype "bidirectional"))
    )
    (net (code "39") (name "unconnected-(U2-PA8-Pad29)") (class "Default")
      (node (ref "U2") (pin "29") (pinfunction "PA8_29") (pintype "bidirectional"))
    )
    (net (code "40") (name "unconnected-(U2-PA9-Pad30)") (class "Default")
      (node (ref "U2") (pin "30") (pinfunction "PA9_30") (pintype "bidirectional"))
    )
    (net (code "41") (name "unconnected-(U2-PA10-Pad31)") (class "Default")
      (node (ref "U2") (pin "31") (pinfunction "PA10_31") (pintype "bidirectional"))
    )
    (net (code "42") (name "unconnected-(U2-PA15-Pad38)") (class "Default")
      (node (ref "U2") (pin "38") (pinfunction "PA15_38") (pintype "bidirectional"))
    )
    (net (code "43") (name "unconnected-(U2-PB0-Pad18)") (class "Default")
      (node (ref "U2") (pin "18") (pinfunction "PB0_18") (pintype "bidirectional"))
    )
    (net (code "44") (name "unconnected-(U2-PB1-Pad19)") (class "Default")
      (node (ref "U2") (pin "19") (pinfunction "PB1_19") (pintype "bidirectional"))
    )
    (net (code "45") (name "unconnected-(U2-PB2-Pad20)") (class "Default")
      (node (ref "U2") (pin "20") (pinfunction "PB2_20") (pintype "bidirectional"))
    )
    (net (code "46") (name "unconnected-(U2-PB7-Pad43)") (class "Default")
      (node (ref "U2") (pin "43") (pinfunction "PB7_43") (pintype "bidirectional"))
    )
    (net (code "47") (name "unconnected-(U2-PB8-Pad45)") (class "Default")
      (node (ref "U2") (pin "45") (pinfunction "PB8_45") (pintype "bidirectional"))
    )
    (net (code "48") (name "unconnected-(U2-PB9-Pad46)") (class "Default")
      (node (ref "U2") (pin "46") (pinfunction "PB9_46") (pintype "bidirectional"))
    )
    (net (code "49") (name "unconnected-(U2-PB10-Pad21)") (class "Default")
      (node (ref "U2") (pin "21") (pinfunction "PB10_21") (pintype "bidirectional"))
    )
    (net (code "50") (name "unconnected-(U2-PB11-Pad22)") (class "Default")
      (node (ref "U2") (pin "22") (pinfunction "PB11_22") (pintype "bidirectional"))
    )
    (net (code "51") (name "unconnected-(U2-PC13-TAMPER-RTC-Pad2)") (class "Default")
      (node (ref "U2") (pin "2") (pinfunction "PC13-TAMPER-RTC_2") (pintype "bidirectional"))
    )
    (net (code "52") (name "unconnected-(U2-PC14-OSC32_IN-Pad3)") (class "Default")
      (node (ref "U2") (pin "3") (pinfunction "PC14-OSC32_IN_3") (pintype "bidirectional"))
    )
    (net (code "53") (name "unconnected-(U2-PC15-OSC32_OUT-Pad4)") (class "Default")
      (node (ref "U2") (pin "4") (pinfunction "PC15-OSC32_OUT_4") (pintype "bidirectional"))
    )
  )
)
